# 16-Relay.net
KiCad netlist of a schematic drawn in Altium Designer
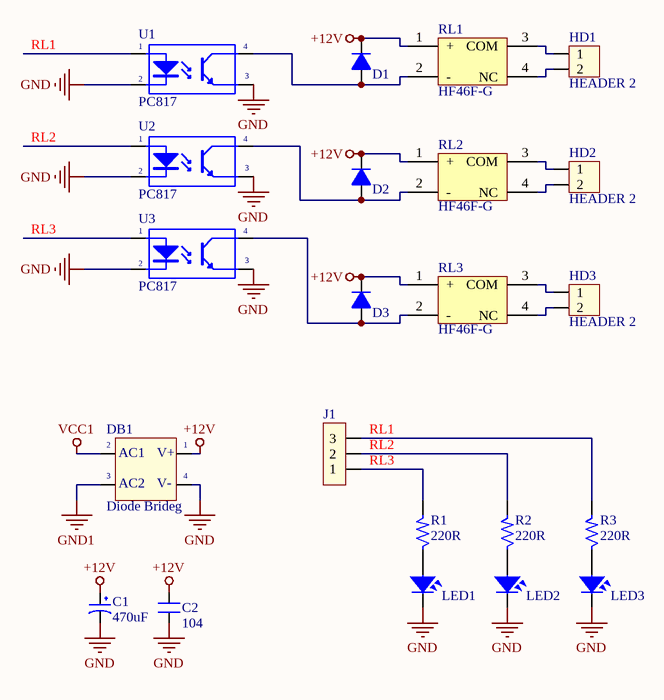
[diagram p0: 16-Relay.SchDoc]

(export (version "E")
  (design (tool "Eeschema 10.0.6"))
  (components
    (comp (ref "C1")
      (value "470uF")
      (footprint "C-ALU-D6.5")
      (description "Cap P  0,1uF < 22uF , 16 - 50V")
      (libsource (lib "PART") (part "CP1"))
    )
    (comp (ref "C2")
      (value "104")
      (footprint "C-0805")
      (fields (field (name "DESIGNED BY") "VanDungEvn"))
      (libsource (lib "syhaunguyen") (part "CN"))
    )
    (comp (ref "D1")
      (value "1N4148")
      (footprint "D-DO213-AA")
      (description "Diode 1A")
      (libsource (lib "PART") (part "D1A"))
    )
    (comp (ref "D2")
      (value "1N4148")
      (footprint "D-DO213-AA")
      (description "Diode 1A")
      (libsource (lib "PART") (part "D1A"))
    )
    (comp (ref "D3")
      (value "1N4148")
      (footprint "D-DO213-AA")
      (description "Diode 1A")
      (libsource (lib "PART") (part "D1A"))
    )
    (comp (ref "DB1")
      (value "Diode Brideg")
      (footprint "D-DB-1A-SMD")
      (description "Convert AC to DC voltage, 4 pin")
      (libsource (lib "PART") (part "DB"))
    )
    (comp (ref "HD1")
      (value "HEADER 2")
      (footprint "TER-KF301-2")
      (description "Header 2 (Green)")
      (libsource (lib "PART") (part "Hed2"))
    )
    (comp (ref "HD2")
      (value "HEADER 2")
      (footprint "TER-KF301-2")
      (description "Header 2 (Green)")
      (libsource (lib "PART") (part "Hed2"))
    )
    (comp (ref "HD3")
      (value "HEADER 2")
      (footprint "TER-KF301-2")
      (description "Header 2 (Green)")
      (libsource (lib "PART") (part "Hed2"))
    )
    (comp (ref "J1") (value "Jumper 3") (footprint "JP3") (libsource (lib "syhaunguyen") (part "JP3")))
    (comp (ref "LED1")
      (value "LED")
      (footprint "LED-0805")
      (description "LED Single colour Green and Red")
      (libsource (lib "syhaunguyen") (part "LED"))
    )
    (comp (ref "LED2")
      (value "LED")
      (footprint "LED-0805")
      (description "LED Single colour Green and Red")
      (libsource (lib "syhaunguyen") (part "LED"))
    )
    (comp (ref "LED3")
      (value "LED")
      (footprint "LED-0805")
      (description "LED Single colour Green and Red")
      (libsource (lib "syhaunguyen") (part "LED"))
    )
    (comp (ref "R1")
      (value "220R")
      (footprint "R-0805")
      (description "Resistor 1/4W")
      (libsource (lib "syhaunguyen") (part "R"))
    )
    (comp (ref "R2")
      (value "220R")
      (footprint "R-0805")
      (description "Resistor 1/4W")
      (libsource (lib "syhaunguyen") (part "R"))
    )
    (comp (ref "R3")
      (value "220R")
      (footprint "R-0805")
      (description "Resistor 1/4W")
      (libsource (lib "syhaunguyen") (part "R"))
    )
    (comp (ref "RL1") (value "HF46F-G") (libsource (lib "doAnTotNghiep2017Lib") (part "HF46F-G")))
    (comp (ref "RL2") (value "HF46F-G") (libsource (lib "doAnTotNghiep2017Lib") (part "HF46F-G")))
    (comp (ref "RL3") (value "HF46F-G") (libsource (lib "doAnTotNghiep2017Lib") (part "HF46F-G")))
    (comp (ref "U1")
      (value "PC817")
      (footprint "PC817")
      (description "Single Opto")
      (libsource (lib "syhaunguyen") (part "PC817"))
    )
    (comp (ref "U2")
      (value "PC817")
      (footprint "PC817")
      (description "Single Opto")
      (libsource (lib "syhaunguyen") (part "PC817"))
    )
    (comp (ref "U3")
      (value "PC817")
      (footprint "PC817")
      (description "Single Opto")
      (libsource (lib "syhaunguyen") (part "PC817"))
    )
  )
  (nets
    (net (code "1") (name "+12V") (class "Default")
      (node (ref "C1") (pin "1") (pinfunction "1_1") (pintype "passive"))
      (node (ref "C2") (pin "2") (pinfunction "2_2") (pintype "passive"))
      (node (ref "D1") (pin "2") (pinfunction "K_2") (pintype "passive"))
      (node (ref "D2") (pin "2") (pinfunction "K_2") (pintype "passive"))
      (node (ref "D3") (pin "2") (pinfunction "K_2") (pintype "passive"))
      (node (ref "DB1") (pin "3") (pinfunction "AC2_3") (pintype "passive"))
      (node (ref "RL1") (pin "1") (pinfunction "+_1") (pintype "passive"))
      (node (ref "RL2") (pin "1") (pinfunction "+_1") (pintype "passive"))
      (node (ref "RL3") (pin "1") (pinfunction "+_1") (pintype "passive"))
    )
    (net (code "2") (name "/RL1") (class "Default")
      (node (ref "J1") (pin "3") (pinfunction "3_3") (pintype "passive"))
      (node (ref "R3") (pin "2") (pinfunction "2_2") (pintype "passive"))
      (node (ref "U1") (pin "1") (pinfunction "A_1") (pintype "passive"))
    )
    (net (code "3") (name "/RL2") (class "Default")
      (node (ref "J1") (pin "2") (pinfunction "2_2") (pintype "passive"))
      (node (ref "R2") (pin "2") (pinfunction "2_2") (pintype "passive"))
      (node (ref "U2") (pin "1") (pinfunction "A_1") (pintype "passive"))
    )
    (net (code "4") (name "/RL3") (class "Default")
      (node (ref "J1") (pin "1") (pinfunction "1_1") (pintype "passive"))
      (node (ref "R1") (pin "2") (pinfunction "2_2") (pintype "passive"))
      (node (ref "U3") (pin "1") (pinfunction "A_1") (pintype "passive"))
    )
    (net (code "5") (name "GND") (class "Default")
      (node (ref "C1") (pin "2") (pinfunction "2_2") (pintype "passive"))
      (node (ref "C2") (pin "1") (pinfunction "1_1") (pintype "passive"))
      (node (ref "DB1") (pin "4") (pinfunction "-V_OUT_4") (pintype "passive"))
      (node (ref "LED1") (pin "2") (pinfunction "2_2") (pintype "passive"))
      (node (ref "LED2") (pin "2") (pinfunction "2_2") (pintype "passive"))
      (node (ref "LED3") (pin "2") (pinfunction "2_2") (pintype "passive"))
      (node (ref "U1") (pin "2") (pinfunction "K_2") (pintype "passive"))
      (node (ref "U1") (pin "3") (pinfunction "E_3") (pintype "passive"))
      (node (ref "U2") (pin "2") (pinfunction "K_2") (pintype "passive"))
      (node (ref "U2") (pin "3") (pinfunction "E_3") (pintype "passive"))
      (node (ref "U3") (pin "2") (pinfunction "K_2") (pintype "passive"))
      (node (ref "U3") (pin "3") (pinfunction "E_3") (pintype "passive"))
    )
    (net (code "6") (name "GND1") (class "Default")
      (node (ref "DB1") (pin "1") (pinfunction "+V_OUT_1") (pintype "passive"))
    )
    (net (code "7") (name "Net-(D1-A)") (class "Default")
      (node (ref "D1") (pin "1") (pinfunction "A_1") (pintype "passive"))
      (node (ref "RL1") (pin "2") (pinfunction "-_2") (pintype "passive"))
      (node (ref "U1") (pin "4") (pinfunction "C_4") (pintype "passive"))
    )
    (net (code "8") (name "Net-(D2-A)") (class "Default")
      (node (ref "D2") (pin "1") (pinfunction "A_1") (pintype "passive"))
      (node (ref "RL2") (pin "2") (pinfunction "-_2") (pintype "passive"))
      (node (ref "U2") (pin "4") (pinfunction "C_4") (pintype "passive"))
    )
    (net (code "9") (name "Net-(D3-A)") (class "Default")
      (node (ref "D3") (pin "1") (pinfunction "A_1") (pintype "passive"))
      (node (ref "RL3") (pin "2") (pinfunction "-_2") (pintype "passive"))
      (node (ref "U3") (pin "4") (pinfunction "C_4") (pintype "passive"))
    )
    (net (code "10") (name "Net-(LED1-Pad1)") (class "Default")
      (node (ref "LED1") (pin "1") (pinfunction "1_1") (pintype "passive"))
      (node (ref "R1") (pin "1") (pinfunction "1_1") (pintype "passive"))
    )
    (net (code "11") (name "Net-(LED2-Pad1)") (class "Default")
      (node (ref "LED2") (pin "1") (pinfunction "1_1") (pintype "passive"))
      (node (ref "R2") (pin "1") (pinfunction "1_1") (pintype "passive"))
    )
    (net (code "12") (name "Net-(LED3-Pad1)") (class "Default")
      (node (ref "LED3") (pin "1") (pinfunction "1_1") (pintype "passive"))
      (node (ref "R3") (pin "1") (pinfunction "1_1") (pintype "passive"))
    )
    (net (code "13") (name "Net-(RL1-COM)") (class "Default")
      (node (ref "HD1") (pin "1") (pinfunction "1_1") (pintype "passive"))
      (node (ref "RL1") (pin "3") (pinfunction "COM_3") (pintype "passive"))
    )
    (net (code "14") (name "Net-(RL1-NC)") (class "Default")
      (node (ref "HD1") (pin "2") (pinfunction "2_2") (pintype "passive"))
      (node (ref "RL1") (pin "4") (pinfunction "NC_4") (pintype "passive"))
    )
    (net (code "15") (name "Net-(RL2-COM)") (class "Default")
      (node (ref "HD2") (pin "1") (pinfunction "1_1") (pintype "passive"))
      (node (ref "RL2") (pin "3") (pinfunction "COM_3") (pintype "passive"))
    )
    (net (code "16") (name "Net-(RL2-NC)") (class "Default")
      (node (ref "HD2") (pin "2") (pinfunction "2_2") (pintype "passive"))
      (node (ref "RL2") (pin "4") (pinfunction "NC_4") (pintype "passive"))
    )
    (net (code "17") (name "Net-(RL3-COM)") (class "Default")
      (node (ref "HD3") (pin "1") (pinfunction "1_1") (pintype "passive"))
      (node (ref "RL3") (pin "3") (pinfunction "COM_3") (pintype "passive"))
    )
    (net (code "18") (name "Net-(RL3-NC)") (class "Default")
      (node (ref "HD3") (pin "2") (pinfunction "2_2") (pintype "passive"))
      (node (ref "RL3") (pin "4") (pinfunction "NC_4") (pintype "passive"))
    )
    (net (code "19") (name "VCC1") (class "Default")
      (node (ref "DB1") (pin "2") (pinfunction "AC1_2") (pintype "passive"))
    )
  )
)
